# PowerAmpTA7270.net
KiCad netlist of a schematic drawn in EAGLE
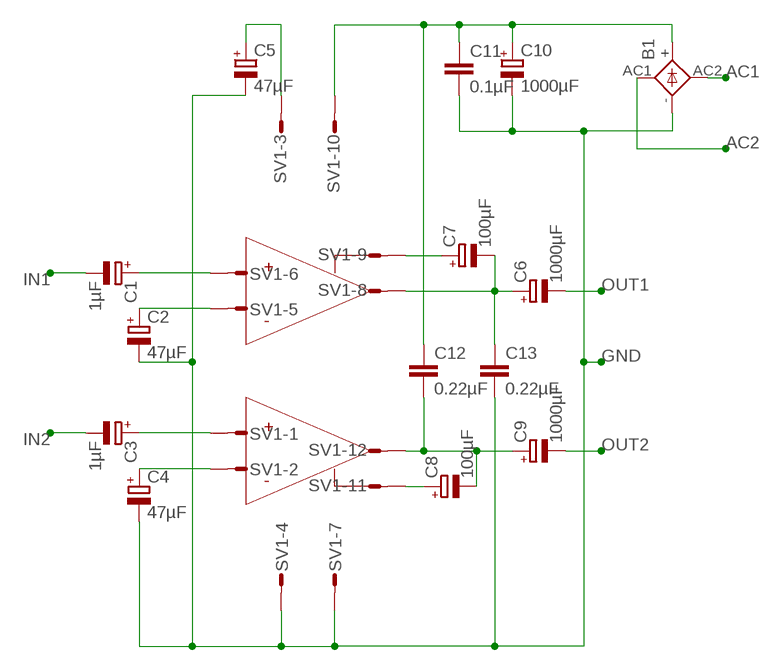
[diagram p0: schematic, sheet 1]

(export (version "E")
  (design (tool "Eeschema 10.0.6"))
  (components
    (comp (ref "B1")
      (value "FB15A")
      (footprint "eagle-import:FB15A")
      (libsource (lib "eagle-import") (part "FB15A"))
    )
    (comp (ref "C1")
      (value "1µF")
      (footprint "eagle-import:E15-5")
      (libsource (lib "eagle-import") (part "CPOL-EUE15-5AXIAL"))
    )
    (comp (ref "C2")
      (value "47µF")
      (footprint "eagle-import:B45181B")
      (libsource (lib "eagle-import") (part "CPOL-EUB45181B"))
    )
    (comp (ref "C3")
      (value "1µF")
      (footprint "eagle-import:E15-5")
      (libsource (lib "eagle-import") (part "CPOL-EUE15-5AXIAL"))
    )
    (comp (ref "C4")
      (value "47µF")
      (footprint "eagle-import:B45181B")
      (libsource (lib "eagle-import") (part "CPOL-EUB45181B"))
    )
    (comp (ref "C5")
      (value "47µF")
      (footprint "eagle-import:B45181B")
      (libsource (lib "eagle-import") (part "CPOL-EUB45181B"))
    )
    (comp (ref "C6")
      (value "1000µF")
      (footprint "eagle-import:E5-13")
      (libsource (lib "eagle-import") (part "CPOL-EUE5-13"))
    )
    (comp (ref "C7")
      (value "100µF")
      (footprint "eagle-import:E3,5-10")
      (libsource (lib "eagle-import") (part "CPOL-EUE3.5-10"))
    )
    (comp (ref "C8")
      (value "100µF")
      (footprint "eagle-import:E3,5-10")
      (libsource (lib "eagle-import") (part "CPOL-EUE3.5-10"))
    )
    (comp (ref "C9")
      (value "1000µF")
      (footprint "eagle-import:E5-13")
      (libsource (lib "eagle-import") (part "CPOL-EUE5-13"))
    )
    (comp (ref "C10")
      (value "1000µF")
      (footprint "eagle-import:E45-18")
      (libsource (lib "eagle-import") (part "CPOL-EUE45-18AXIAL"))
    )
    (comp (ref "C11")
      (value "0.1µF")
      (footprint "eagle-import:C050-025X075")
      (libsource (lib "eagle-import") (part "C-EU050-025X075"))
    )
    (comp (ref "C12")
      (value "0.22µF")
      (footprint "eagle-import:C050-025X075")
      (libsource (lib "eagle-import") (part "C-EU050-025X075"))
    )
    (comp (ref "C13")
      (value "0.22µF")
      (footprint "eagle-import:C050-025X075")
      (libsource (lib "eagle-import") (part "C-EU050-025X075"))
    )
    (comp (ref "SV1")
      (value "S12P")
      (footprint "eagle-import:S12P")
      (libsource (lib "eagle-import") (part "S12P"))
    )
  )
  (nets
    (net (code "1") (name "/AC1") (class "Default")
      (node (ref "B1") (pin "AC2") (pinfunction "AC2_AC2") (pintype "passive"))
    )
    (net (code "2") (name "/AC2") (class "Default")
      (node (ref "B1") (pin "AC1") (pinfunction "AC1_AC1") (pintype "passive"))
    )
    (net (code "3") (name "/GND") (class "Default")
      (node (ref "B1") (pin "-") (pinfunction "-_-") (pintype "passive"))
      (node (ref "C10") (pin "-") (pinfunction "-_-") (pintype "passive"))
      (node (ref "C11") (pin "2") (pinfunction "2_2") (pintype "passive"))
      (node (ref "C13") (pin "2") (pinfunction "2_2") (pintype "passive"))
      (node (ref "C2") (pin "-") (pinfunction "-_-") (pintype "passive"))
      (node (ref "C4") (pin "-") (pinfunction "-_-") (pintype "passive"))
      (node (ref "C5") (pin "-") (pinfunction "-_-") (pintype "passive"))
      (node (ref "SV1") (pin "4") (pinfunction "S_4") (pintype "passive"))
      (node (ref "SV1") (pin "7") (pinfunction "S_7") (pintype "passive"))
    )
    (net (code "4") (name "/IN1") (class "Default")
      (node (ref "C1") (pin "-") (pinfunction "-_-") (pintype "passive"))
    )
    (net (code "5") (name "/IN2") (class "Default")
      (node (ref "C3") (pin "-") (pinfunction "-_-") (pintype "passive"))
    )
    (net (code "6") (name "/OUT1") (class "Default")
      (node (ref "C6") (pin "-") (pinfunction "-_-") (pintype "passive"))
    )
    (net (code "7") (name "/OUT2") (class "Default")
      (node (ref "C9") (pin "-") (pinfunction "-_-") (pintype "passive"))
    )
    (net (code "8") (name "Net-(SV1A-S)") (class "Default")
      (node (ref "C3") (pin "+") (pinfunction "+_+") (pintype "passive"))
      (node (ref "SV1") (pin "1") (pinfunction "S_1") (pintype "passive"))
    )
    (net (code "9") (name "Net-(SV1B-S)") (class "Default")
      (node (ref "B1") (pin "+") (pinfunction "+_+") (pintype "passive"))
      (node (ref "C10") (pin "+") (pinfunction "+_+") (pintype "passive"))
      (node (ref "C11") (pin "1") (pinfunction "1_1") (pintype "passive"))
      (node (ref "C12") (pin "1") (pinfunction "1_1") (pintype "passive"))
      (node (ref "SV1") (pin "10") (pinfunction "S_10") (pintype "passive"))
    )
    (net (code "10") (name "Net-(SV1C-S)") (class "Default")
      (node (ref "C8") (pin "+") (pinfunction "+_+") (pintype "passive"))
      (node (ref "SV1") (pin "11") (pinfunction "S_11") (pintype "passive"))
    )
    (net (code "11") (name "Net-(SV1D-S)") (class "Default")
      (node (ref "C12") (pin "2") (pinfunction "2_2") (pintype "passive"))
      (node (ref "C8") (pin "-") (pinfunction "-_-") (pintype "passive"))
      (node (ref "C9") (pin "+") (pinfunction "+_+") (pintype "passive"))
      (node (ref "SV1") (pin "12") (pinfunction "S_12") (pintype "passive"))
    )
    (net (code "12") (name "Net-(SV1E-S)") (class "Default")
      (node (ref "C4") (pin "+") (pinfunction "+_+") (pintype "passive"))
      (node (ref "SV1") (pin "2") (pinfunction "S_2") (pintype "passive"))
    )
    (net (code "13") (name "Net-(SV1F-S)") (class "Default")
      (node (ref "C5") (pin "+") (pinfunction "+_+") (pintype "passive"))
      (node (ref "SV1") (pin "3") (pinfunction "S_3") (pintype "passive"))
    )
    (net (code "14") (name "Net-(SV1H-S)") (class "Default")
      (node (ref "C2") (pin "+") (pinfunction "+_+") (pintype "passive"))
      (node (ref "SV1") (pin "5") (pinfunction "S_5") (pintype "passive"))
    )
    (net (code "15") (name "Net-(SV1I-S)") (class "Default")
      (node (ref "C1") (pin "+") (pinfunction "+_+") (pintype "passive"))
      (node (ref "SV1") (pin "6") (pinfunction "S_6") (pintype "passive"))
    )
    (net (code "16") (name "Net-(SV1K-S)") (class "Default")
      (node (ref "C13") (pin "1") (pinfunction "1_1") (pintype "passive"))
      (node (ref "C6") (pin "+") (pinfunction "+_+") (pintype "passive"))
      (node (ref "C7") (pin "-") (pinfunction "-_-") (pintype "passive"))
      (node (ref "SV1") (pin "8") (pinfunction "S_8") (pintype "passive"))
    )
    (net (code "17") (name "Net-(SV1L-S)") (class "Default")
      (node (ref "C7") (pin "+") (pinfunction "+_+") (pintype "passive"))
      (node (ref "SV1") (pin "9") (pinfunction "S_9") (pintype "passive"))
    )
  )
)
